# electrode_module3_3.net
KiCad netlist of a schematic drawn in Altium Designer
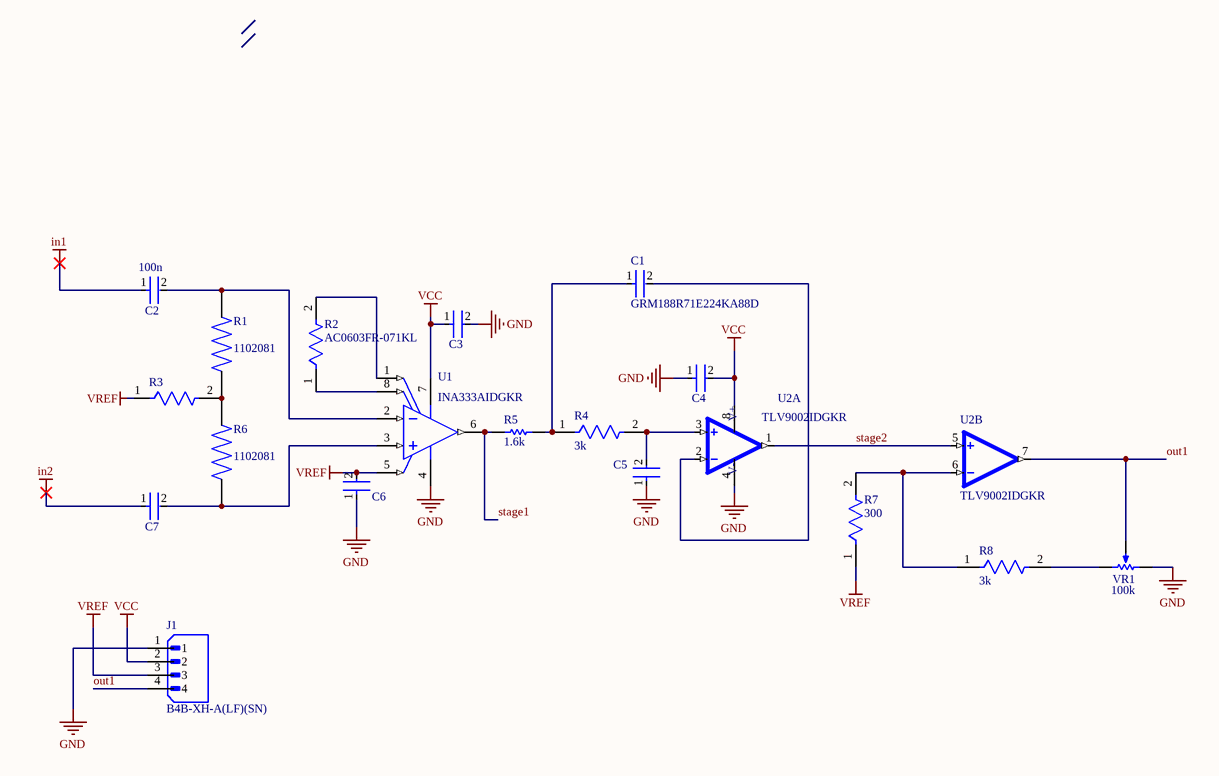
[diagram p0: electrode_module3.3.SchDoc]

(export (version "E")
  (design (tool "Eeschema 10.0.6"))
  (components
    (comp (ref "C1")
      (value "GRM188R71E224KA88D")
      (footprint "FP-GRM188-0_1-e0_2_0_5-IPC_C")
      (description "Chip Multilayer Ceramic Capacitors for General Purpose, 0603, 0.22uF, X7R, 15%, 10%, 25V")
      (fields (field (name "TOLERANCE") "10%") (field (name "VOLTAGE") "50V"))
      (libsource (lib "Altium Content Vault") (part "11868f565c42a9108669ba33697ecf6"))
    )
    (comp (ref "C2")
      (value "100n")
      (footprint "FP-CGA3E-0_3-0_1-IPC_A")
      (description "Cap Ceramic 100nF 50V X7R 10% Pad SMD 0603 +125°C Automotive T/R")
      (fields (field (name "TOLERANCE") "10%") (field (name "VOLTAGE") "50V"))
      (libsource (lib "Altium Content Vault") (part "b4654b650e69147ec39a6b967a45e02"))
    )
    (comp (ref "C3")
      (value "CGA3E2X7R1H104K080AA")
      (footprint "FP-CGA3E-0_3-0_1-IPC_A")
      (description "Cap Ceramic 100nF 50V X7R 10% Pad SMD 0603 +125°C Automotive T/R")
      (fields (field (name "TOLERANCE") "10%") (field (name "VOLTAGE") "50V"))
      (libsource (lib "Altium Content Vault") (part "b4654b650e69147ec39a6b967a45e02"))
    )
    (comp (ref "C4")
      (value "CGA3E2X7R1H104K080AA")
      (footprint "FP-CGA3E-0_3-0_1-IPC_A")
      (description "Cap Ceramic 100nF 50V X7R 10% Pad SMD 0603 +125°C Automotive T/R")
      (fields (field (name "TOLERANCE") "10%") (field (name "VOLTAGE") "50V"))
      (libsource (lib "Altium Content Vault") (part "b4654b650e69147ec39a6b967a45e02"))
    )
    (comp (ref "C5")
      (value "CGA3E2X7R1H104K080AA")
      (footprint "FP-CGA3E-0_3-0_1-IPC_A")
      (description "Cap Ceramic 100nF 50V X7R 10% Pad SMD 0603 +125°C Automotive T/R")
      (fields (field (name "TOLERANCE") "10%") (field (name "VOLTAGE") "50V"))
      (libsource (lib "Altium Content Vault") (part "b4654b650e69147ec39a6b967a45e02"))
    )
    (comp (ref "C6")
      (value "CGA3E2X7R1H104K080AA")
      (footprint "FP-CGA3E-0_3-0_1-IPC_A")
      (description "Cap Ceramic 100nF 50V X7R 10% Pad SMD 0603 +125°C Automotive T/R")
      (fields (field (name "TOLERANCE") "10%") (field (name "VOLTAGE") "50V"))
      (libsource (lib "Altium Content Vault") (part "b4654b650e69147ec39a6b967a45e02"))
    )
    (comp (ref "C7")
      (value "100n")
      (footprint "FP-CGA3E-0_3-0_1-IPC_A")
      (description "Cap Ceramic 100nF 50V X7R 10% Pad SMD 0603 +125°C Automotive T/R")
      (fields (field (name "TOLERANCE") "10%") (field (name "VOLTAGE") "50V"))
      (libsource (lib "Altium Content Vault") (part "b4654b650e69147ec39a6b967a45e02"))
    )
    (comp (ref "J1")
      (value "B4B-XH-A(LF)(SN)")
      (footprint "JST_B4B-XH-A(LF)(SN)")
      (description "Connector Header Through Hole 4 position 0.098 (2.50mm)")
      (fields (field (name "MF") "JST Sales"))
      (libsource (lib "B4B-XH-A_LF__SN_") (part "B4B-XH-A(LF)(SN)"))
    )
    (comp (ref "R1")
      (value "RT0603BRD071ML")
      (footprint "RESC1608X55N")
      (description "1 MOhms Â±0.1% 0.1W, 1/10W Chip Resistor 0603 (1608 Metric) Thin Film")
      (fields
        (field (name "MF") "Yageo")
        (field (name "DIGI-KEY_PART_NUMBER") "YAG4498CT-ND")
        (field (name "SUPPLIER PART NUMBER 1") "1102081")
      )
      (libsource (lib "RT0603BRD071ML") (part "RT0603BRD071ML"))
    )
    (comp (ref "R2")
      (value "AC0603FR-071KL")
      (footprint "FP-AC0603-IPC_B")
      (description "RES 1kΩ 1.00% 0.1W 0603")
      (fields (field (name "TOLERANCE") "1%"))
      (libsource (lib "Altium Content Vault") (part "1029c3af85768c4190bb7ad29bc67b5"))
    )
    (comp (ref "R3")
      (value "ERA-3AEB103V")
      (footprint "FP-ERA3A-IPC_C")
      (description "RES SMD 10K OHM 0.1% 1/10W 0603")
      (fields (field (name "TOLERANCE") "0.1%"))
      (libsource (lib "Altium Content Vault") (part "4e5f8b3dd332802e91518312df5df73"))
    )
    (comp (ref "R4")
      (value "3k")
      (footprint "FP-CRCW0603-e3-MFG")
      (description "RES Thick Film, 3kΩ, 1%, 0.1W, 100ppm/°C, 0603")
      (fields (field (name "TOLERANCE") "1%"))
      (libsource (lib "Altium Content Vault") (part "1029c3af85768c4190bb7ad29bc67b5"))
    )
    (comp (ref "R5")
      (value "1.6k")
      (footprint "RESC1609X50X30LL10T20")
      (fields (field (name "PART NUMBER") "CRCW06031K60FKEA") (field (name "MANUFACTURER") "Vishay Dale"))
      (libsource (lib "Altium Content Vault") (part "RES"))
    )
    (comp (ref "R6")
      (value "RT0603BRD071ML")
      (footprint "RESC1608X55N")
      (description "1 MOhms Â±0.1% 0.1W, 1/10W Chip Resistor 0603 (1608 Metric) Thin Film")
      (fields
        (field (name "MF") "Yageo")
        (field (name "DIGI-KEY_PART_NUMBER") "YAG4498CT-ND")
        (field (name "SUPPLIER PART NUMBER 1") "1102081")
      )
      (libsource (lib "RT0603BRD071ML") (part "RT0603BRD071ML"))
    )
    (comp (ref "R7")
      (value "300")
      (footprint "FP-CRCW0603-e3-IPC_A")
      (description "RES Thick Film, 300Ω, 1%, 0.1W, 100ppm/°C, 0603")
      (fields (field (name "TOLERANCE") "1%"))
      (libsource (lib "Altium Content Vault") (part "1029c3af85768c4190bb7ad29bc67b5"))
    )
    (comp (ref "R8")
      (value "3k")
      (footprint "FP-CRCW0603-e3-MFG")
      (description "RES Thick Film, 3kΩ, 1%, 0.1W, 100ppm/°C, 0603")
      (fields (field (name "TOLERANCE") "1%"))
      (libsource (lib "Altium Content Vault") (part "1029c3af85768c4190bb7ad29bc67b5"))
    )
    (comp (ref "U1")
      (value "INA333AIDGKR")
      (footprint "DGK0008A_N")
      (fields (field (name "MANUFACTURER") "Texas Instruments"))
      (libsource (lib "Altium Content Vault") (part "TI-INAXXXXXX8"))
    )
    (comp (ref "U2")
      (value "TLV9002IDGKR")
      (footprint "SOP65P490X110-8N")
      (description "Dual, 5.5-V, 1-MHz, RRIO operational amplifier for cost-optimized applications")
      (fields (field (name "MF") "Texas Instruments"))
      (libsource (lib "TLV9002IDGKR") (part "TLV9002IDGKR"))
    )
    (comp (ref "VR1")
      (value "100k")
      (footprint "BOUR-3362P")
      (description "Square Trimpot(R) Trimming Potentiometer, 100 KOhm, 300 V, -55 to 125 degC, 3-Pin THD, RoHS, Tube")
      (fields (field (name "TOLERANCE") "1%"))
      (libsource (lib "Altium Content Vault") (part "RES-POT-3"))
    )
  )
  (nets
    (net (code "1") (name "/out1") (class "Default")
      (node (ref "J1") (pin "4") (pinfunction "4_4") (pintype "passive"))
      (node (ref "U2") (pin "7") (pinfunction "OUT2_7") (pintype "output"))
      (node (ref "VR1") (pin "2") (pinfunction "S_2") (pintype "passive"))
    )
    (net (code "2") (name "/stage1") (class "Default")
      (node (ref "R5") (pin "2") (pinfunction "2_2") (pintype "passive"))
      (node (ref "U1") (pin "6") (pinfunction "VOUT_6") (pintype "output"))
    )
    (net (code "3") (name "/stage2") (class "Default")
      (node (ref "U2") (pin "1") (pinfunction "OUT1_1") (pintype "output"))
      (node (ref "U2") (pin "5") (pinfunction "IN2+_5") (pintype "input"))
    )
    (net (code "4") (name "GND") (class "Default")
      (node (ref "C3") (pin "2") (pinfunction "2_2") (pintype "passive"))
      (node (ref "C4") (pin "1") (pinfunction "1_1") (pintype "passive"))
      (node (ref "C5") (pin "1") (pinfunction "1_1") (pintype "passive"))
      (node (ref "C6") (pin "1") (pinfunction "1_1") (pintype "passive"))
      (node (ref "J1") (pin "1") (pinfunction "1_1") (pintype "passive"))
      (node (ref "U1") (pin "4") (pinfunction "V-_4") (pintype "power_in"))
      (node (ref "U2") (pin "4") (pinfunction "V-_4") (pintype "power_in"))
      (node (ref "VR1") (pin "1") (pinfunction "CCW_1") (pintype "passive"))
    )
    (net (code "5") (name "Net-(C1-Pad1)") (class "Default")
      (node (ref "C1") (pin "1") (pinfunction "1_1") (pintype "passive"))
      (node (ref "R4") (pin "1") (pinfunction "1_1") (pintype "passive"))
      (node (ref "R5") (pin "1") (pinfunction "1_1") (pintype "passive"))
    )
    (net (code "6") (name "Net-(R1-Pad1)") (class "Default")
      (node (ref "R1") (pin "1") (pinfunction "1_1") (pintype "passive"))
      (node (ref "R3") (pin "2") (pinfunction "2_2") (pintype "passive"))
      (node (ref "R6") (pin "2") (pinfunction "2_2") (pintype "passive"))
    )
    (net (code "7") (name "Net-(R2-Pad1)") (class "Default")
      (node (ref "R2") (pin "1") (pinfunction "1_1") (pintype "passive"))
      (node (ref "U1") (pin "8") (pinfunction "RG_8") (pintype "input"))
    )
    (net (code "8") (name "Net-(R2-Pad2)") (class "Default")
      (node (ref "R2") (pin "2") (pinfunction "2_2") (pintype "passive"))
      (node (ref "U1") (pin "1") (pinfunction "RG_1") (pintype "input"))
    )
    (net (code "9") (name "Net-(U1-VIN+)") (class "Default")
      (node (ref "C7") (pin "2") (pinfunction "2_2") (pintype "passive"))
      (node (ref "R6") (pin "1") (pinfunction "1_1") (pintype "passive"))
      (node (ref "U1") (pin "3") (pinfunction "VIN+_3") (pintype "input"))
    )
    (net (code "10") (name "Net-(U1-VIN-)") (class "Default")
      (node (ref "C2") (pin "2") (pinfunction "2_2") (pintype "passive"))
      (node (ref "R1") (pin "2") (pinfunction "2_2") (pintype "passive"))
      (node (ref "U1") (pin "2") (pinfunction "VIN-_2") (pintype "input"))
    )
    (net (code "11") (name "Net-(U2A-IN1+)") (class "Default")
      (node (ref "C5") (pin "2") (pinfunction "2_2") (pintype "passive"))
      (node (ref "R4") (pin "2") (pinfunction "2_2") (pintype "passive"))
      (node (ref "U2") (pin "3") (pinfunction "IN1+_3") (pintype "input"))
    )
    (net (code "12") (name "Net-(U2A-IN1-)") (class "Default")
      (node (ref "C1") (pin "2") (pinfunction "2_2") (pintype "passive"))
      (node (ref "U2") (pin "2") (pinfunction "IN1-_2") (pintype "input"))
    )
    (net (code "13") (name "Net-(U2B-IN2-)") (class "Default")
      (node (ref "R7") (pin "2") (pinfunction "2_2") (pintype "passive"))
      (node (ref "R8") (pin "1") (pinfunction "1_1") (pintype "passive"))
      (node (ref "U2") (pin "6") (pinfunction "IN2-_6") (pintype "input"))
    )
    (net (code "14") (name "Net-(VR1-CW)") (class "Default")
      (node (ref "R8") (pin "2") (pinfunction "2_2") (pintype "passive"))
      (node (ref "VR1") (pin "3") (pinfunction "CW_3") (pintype "passive"))
    )
    (net (code "15") (name "VCC") (class "Default")
      (node (ref "C3") (pin "1") (pinfunction "1_1") (pintype "passive"))
      (node (ref "C4") (pin "2") (pinfunction "2_2") (pintype "passive"))
      (node (ref "J1") (pin "2") (pinfunction "2_2") (pintype "passive"))
      (node (ref "U1") (pin "7") (pinfunction "V+_7") (pintype "power_in"))
      (node (ref "U2") (pin "8") (pinfunction "V+_8") (pintype "power_in"))
    )
    (net (code "16") (name "VREF") (class "Default")
      (node (ref "C6") (pin "2") (pinfunction "2_2") (pintype "passive"))
      (node (ref "J1") (pin "3") (pinfunction "3_3") (pintype "passive"))
      (node (ref "R3") (pin "1") (pinfunction "1_1") (pintype "passive"))
      (node (ref "R7") (pin "1") (pinfunction "1_1") (pintype "passive"))
      (node (ref "U1") (pin "5") (pinfunction "REF_5") (pintype "input"))
    )
    (net (code "17") (name "in1") (class "Default")
      (node (ref "C2") (pin "1") (pinfunction "1_1") (pintype "passive"))
    )
    (net (code "18") (name "in2") (class "Default")
      (node (ref "C7") (pin "1") (pinfunction "1_1") (pintype "passive"))
    )
  )
)
